# GND_SATION_PCB_1_02.net
KiCad netlist of a schematic drawn in EAGLE
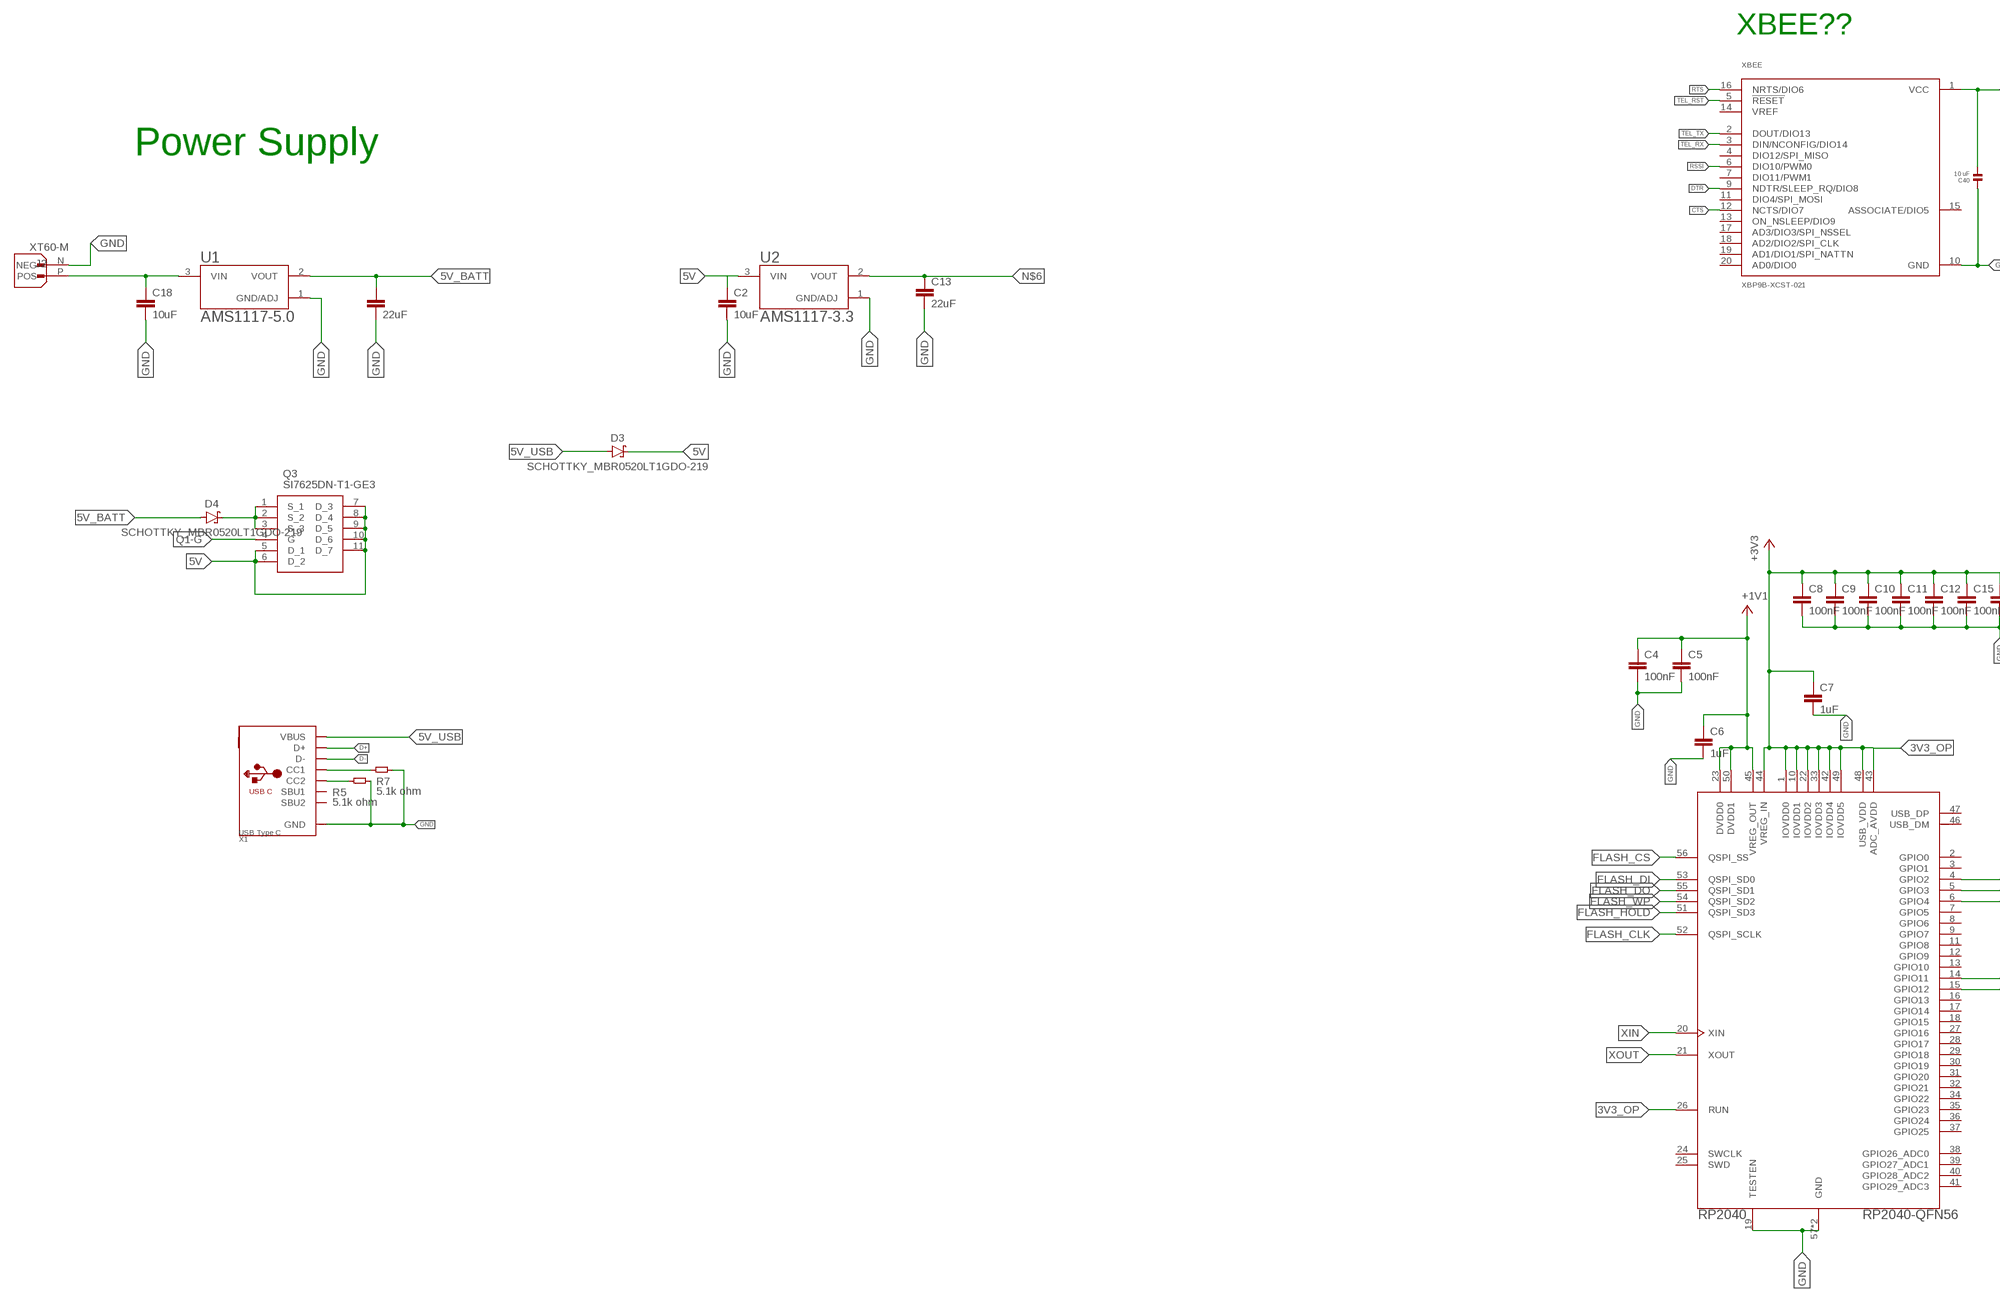
[diagram p0: schematic, sheet 1, part 1 of 2]
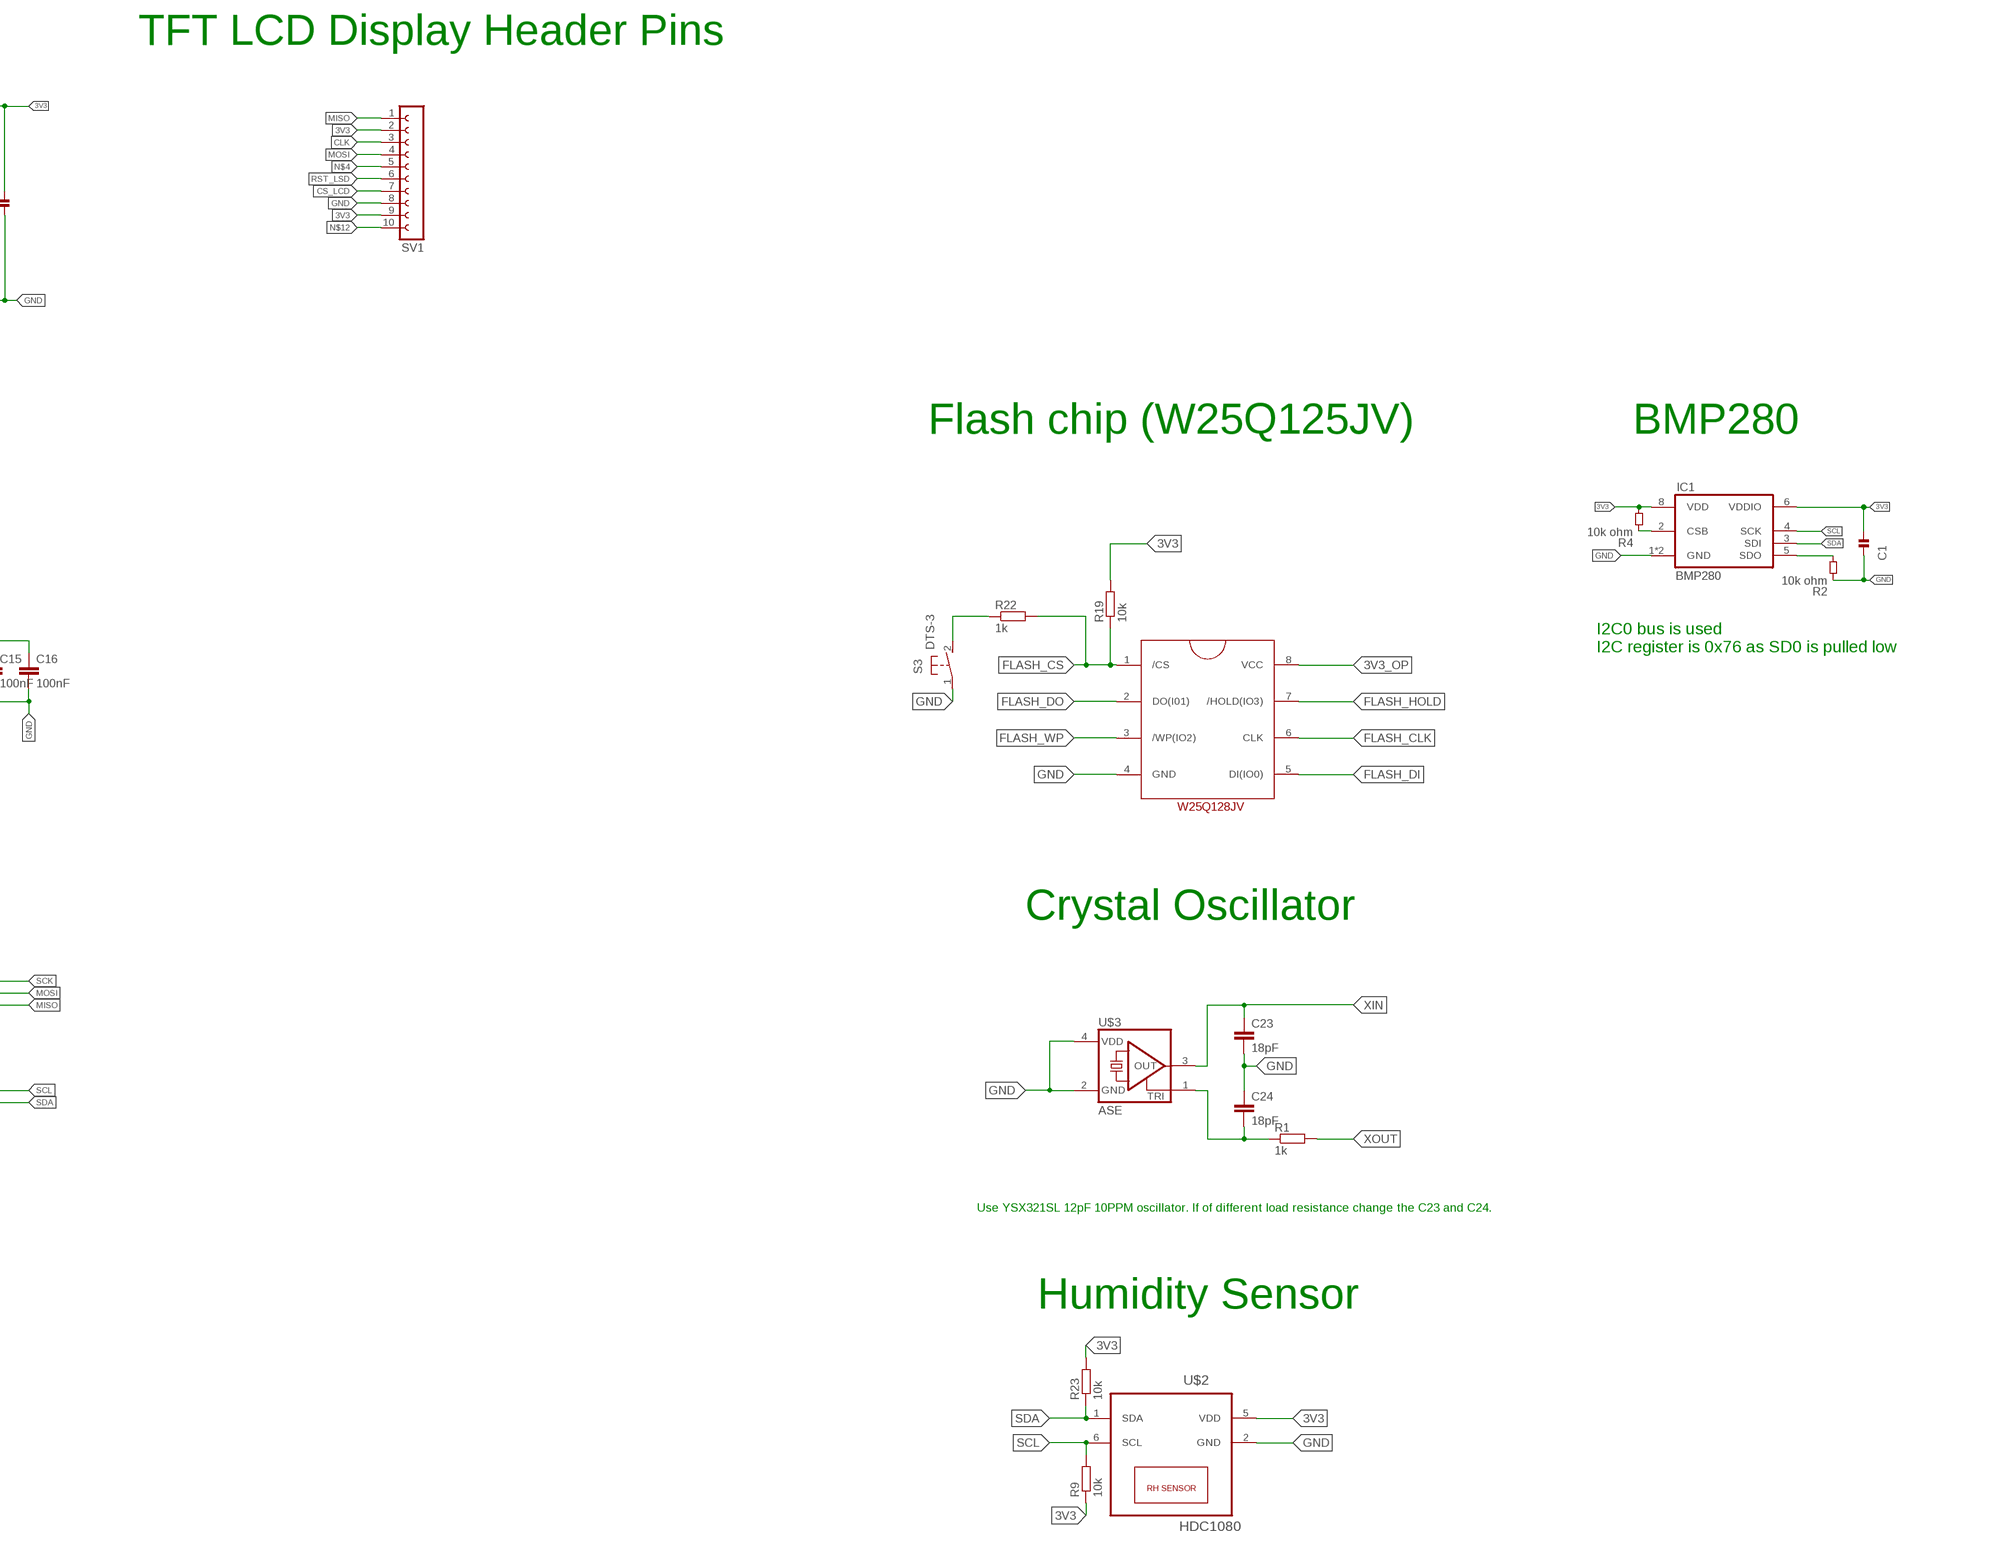
[diagram p1: schematic, sheet 1, part 2 of 2]

(export (version "E")
  (design (tool "Eeschema 10.0.6"))
  (components
    (comp (ref "C1")
      (value "10 uF")
      (footprint "eagle-import:0603")
      (libsource (lib "eagle-import") (part "CAPACITOR.0603"))
    )
    (comp (ref "C2")
      (value "10uF")
      (footprint "eagle-import:C0805")
      (libsource (lib "eagle-import") (part "C-EUC0805"))
    )
    (comp (ref "C3")
      (value "22uF")
      (footprint "eagle-import:C0805")
      (libsource (lib "eagle-import") (part "C-EUC0805"))
    )
    (comp (ref "C4")
      (value "100nF")
      (footprint "eagle-import:C0603")
      (libsource (lib "eagle-import") (part "C-EUC0603"))
    )
    (comp (ref "C5")
      (value "100nF")
      (footprint "eagle-import:C0603")
      (libsource (lib "eagle-import") (part "C-EUC0603"))
    )
    (comp (ref "C6")
      (value "1uF")
      (footprint "eagle-import:C0603")
      (libsource (lib "eagle-import") (part "C-EUC0603"))
    )
    (comp (ref "C7")
      (value "1uF")
      (footprint "eagle-import:C0603")
      (libsource (lib "eagle-import") (part "C-EUC0603"))
    )
    (comp (ref "C8")
      (value "100nF")
      (footprint "eagle-import:C0603")
      (libsource (lib "eagle-import") (part "C-EUC0603"))
    )
    (comp (ref "C9")
      (value "100nF")
      (footprint "eagle-import:C0603")
      (libsource (lib "eagle-import") (part "C-EUC0603"))
    )
    (comp (ref "C10")
      (value "100nF")
      (footprint "eagle-import:C0603")
      (libsource (lib "eagle-import") (part "C-EUC0603"))
    )
    (comp (ref "C11")
      (value "100nF")
      (footprint "eagle-import:C0603")
      (libsource (lib "eagle-import") (part "C-EUC0603"))
    )
    (comp (ref "C12")
      (value "100nF")
      (footprint "eagle-import:C0603")
      (libsource (lib "eagle-import") (part "C-EUC0603"))
    )
    (comp (ref "C13")
      (value "22uF")
      (footprint "eagle-import:C0805")
      (libsource (lib "eagle-import") (part "C-EUC0805"))
    )
    (comp (ref "C15")
      (value "100nF")
      (footprint "eagle-import:C0603")
      (libsource (lib "eagle-import") (part "C-EUC0603"))
    )
    (comp (ref "C16")
      (value "100nF")
      (footprint "eagle-import:C0603")
      (libsource (lib "eagle-import") (part "C-EUC0603"))
    )
    (comp (ref "C18")
      (value "10uF")
      (footprint "eagle-import:C0805")
      (libsource (lib "eagle-import") (part "C-EUC0805"))
    )
    (comp (ref "C23")
      (value "18pF")
      (footprint "eagle-import:C0805")
      (libsource (lib "eagle-import") (part "C-EUC0805"))
    )
    (comp (ref "C24")
      (value "18pF")
      (footprint "eagle-import:C0805")
      (libsource (lib "eagle-import") (part "C-EUC0805"))
    )
    (comp (ref "C40")
      (value "10 uF")
      (footprint "eagle-import:0603")
      (libsource (lib "eagle-import") (part "CAPACITOR.0603"))
    )
    (comp (ref "D3")
      (value "SCHOTTKY_MBR0520LT1GDO-219")
      (footprint "eagle-import:SODFL3718X115")
      (fields (field (name "MANUFACTURER") "onsemi") (field (name "MPN") "MBR0520LT1G"))
      (libsource (lib "eagle-import") (part "SCHOTTKY_DO-219MBR0520LT1G"))
    )
    (comp (ref "D4")
      (value "SCHOTTKY_MBR0520LT1GDO-219")
      (footprint "eagle-import:SODFL3718X115")
      (fields (field (name "MANUFACTURER") "onsemi") (field (name "MPN") "MBR0520LT1G"))
      (libsource (lib "eagle-import") (part "SCHOTTKY_DO-219MBR0520LT1G"))
    )
    (comp (ref "IC1")
      (value "BMP280")
      (footprint "eagle-import:BMP280")
      (libsource (lib "eagle-import") (part "BMP280"))
    )
    (comp (ref "J2")
      (value "XT60-M")
      (footprint "eagle-import:AMASS_XT60-M")
      (fields (field (name "MF") "AMASS"))
      (libsource (lib "eagle-import") (part "XT60-M"))
    )
    (comp (ref "Q3")
      (value "SI7625DN-T1-GE3")
      (footprint "eagle-import:SIS862DNT1GE3")
      (libsource (lib "eagle-import") (part "SI7625DN-T1-GE3"))
    )
    (comp (ref "R1")
      (value "1k")
      (footprint "eagle-import:R0805")
      (libsource (lib "eagle-import") (part "R-EU_R0805"))
    )
    (comp (ref "R2")
      (value "10k ohm")
      (footprint "eagle-import:0603")
      (libsource (lib "eagle-import") (part "RESISTOR.0603"))
    )
    (comp (ref "R4")
      (value "10k ohm")
      (footprint "eagle-import:0603")
      (libsource (lib "eagle-import") (part "RESISTOR.0603"))
    )
    (comp (ref "R5")
      (value "5.1k ohm")
      (footprint "eagle-import:0603")
      (libsource (lib "eagle-import") (part "RESISTOR.0603"))
    )
    (comp (ref "R7")
      (value "5.1k ohm")
      (footprint "eagle-import:0603")
      (libsource (lib "eagle-import") (part "RESISTOR.0603"))
    )
    (comp (ref "R9")
      (value "10k")
      (footprint "eagle-import:R0805")
      (libsource (lib "eagle-import") (part "R-EU_R0805"))
    )
    (comp (ref "R19")
      (value "10k")
      (footprint "eagle-import:R0805")
      (libsource (lib "eagle-import") (part "R-EU_R0805"))
    )
    (comp (ref "R22")
      (value "1k")
      (footprint "eagle-import:R0805")
      (libsource (lib "eagle-import") (part "R-EU_R0805"))
    )
    (comp (ref "R23")
      (value "10k")
      (footprint "eagle-import:R0805")
      (libsource (lib "eagle-import") (part "R-EU_R0805"))
    )
    (comp (ref "RP2040")
      (value "RP2040-QFN56")
      (footprint "eagle-import:RP2040-QFN-56")
      (libsource (lib "eagle-import") (part "RP2040-QFN56"))
    )
    (comp (ref "S3")
      (value "DTS-3")
      (footprint "eagle-import:DTS-3")
      (fields (field (name "MF") "APEM Inc."))
      (libsource (lib "eagle-import") (part "DTS-3"))
    )
    (comp (ref "SV1")
      (value "FE10-1")
      (footprint "eagle-import:FE10")
      (libsource (lib "eagle-import") (part "FE10-1"))
    )
    (comp (ref "U$2")
      (value "HDC1080")
      (footprint "eagle-import:TI-S-PWSON-N6")
      (libsource (lib "eagle-import") (part "HDC1080"))
    )
    (comp (ref "U$3")
      (value "ASE")
      (footprint "eagle-import:ASE")
      (libsource (lib "eagle-import") (part "ASE"))
    )
    (comp (ref "U1")
      (value "AMS1117-5.0")
      (footprint "eagle-import:SOT229P700X180-4N")
      (fields (field (name "MF") "Advanced Monolithic Systems"))
      (libsource (lib "eagle-import") (part "AMS1117-5.0"))
    )
    (comp (ref "U2")
      (value "AMS1117-3.3")
      (footprint "eagle-import:SOT229P700X180-4N")
      (fields (field (name "MF") "Advanced Monolithic Systems"))
      (libsource (lib "eagle-import") (part "AMS1117-3.3"))
    )
    (comp (ref "U4")
      (value "SOIC127P790X216-8NW25Q128JVJSQ")
      (footprint "eagle-import:SOIC127P790X216-8N")
      (libsource (lib "eagle-import") (part "SOIC127P790X216-8NW25Q128JVJSQ"))
    )
    (comp (ref "X1")
      (value "USB Type C")
      (footprint "eagle-import:USB_C_CUSB31-CFM2AX-01-X")
      (libsource (lib "eagle-import") (part "USB_C"))
    )
    (comp (ref "XBEE")
      (value "XBP9B-XCST-021")
      (footprint "eagle-import:DIP2200W51P200L3294H279Q20P")
      (fields (field (name "MF") "Digi International"))
      (libsource (lib "eagle-import") (part "XBP9B-XCST-021"))
    )
  )
  (nets
    (net (code "1") (name "+1V1") (class "Default")
      (node (ref "C4") (pin "1") (pinfunction "1_1") (pintype "passive"))
      (node (ref "C5") (pin "1") (pinfunction "1_1") (pintype "passive"))
      (node (ref "C6") (pin "1") (pinfunction "1_1") (pintype "passive"))
      (node (ref "RP2040") (pin "23") (pinfunction "DVDD0_23") (pintype "power_in"))
      (node (ref "RP2040") (pin "45") (pinfunction "VREG_OUT_45") (pintype "power_in"))
      (node (ref "RP2040") (pin "50") (pinfunction "DVDD1_50") (pintype "power_in"))
    )
    (net (code "2") (name "3V3") (class "Default")
      (node (ref "C1") (pin "2") (pinfunction "2_2") (pintype "bidirectional"))
      (node (ref "C40") (pin "2") (pinfunction "2_2") (pintype "bidirectional"))
      (node (ref "IC1") (pin "6") (pinfunction "VDDIO_6") (pintype "power_in"))
      (node (ref "IC1") (pin "8") (pinfunction "VDD_8") (pintype "power_in"))
      (node (ref "R19") (pin "2") (pinfunction "2_2") (pintype "passive"))
      (node (ref "R23") (pin "2") (pinfunction "2_2") (pintype "passive"))
      (node (ref "R4") (pin "2") (pinfunction "2_2") (pintype "bidirectional"))
      (node (ref "R9") (pin "1") (pinfunction "1_1") (pintype "passive"))
      (node (ref "SV1") (pin "2") (pinfunction "2_2") (pintype "passive"))
      (node (ref "SV1") (pin "9") (pinfunction "9_9") (pintype "passive"))
      (node (ref "U$2") (pin "5") (pinfunction "VDD_5") (pintype "output"))
      (node (ref "XBEE") (pin "1") (pinfunction "VCC_1") (pintype "power_in"))
    )
    (net (code "3") (name "3V3_OP") (class "Default")
      (node (ref "C10") (pin "1") (pinfunction "1_1") (pintype "passive"))
      (node (ref "C11") (pin "1") (pinfunction "1_1") (pintype "passive"))
      (node (ref "C12") (pin "1") (pinfunction "1_1") (pintype "passive"))
      (node (ref "C15") (pin "1") (pinfunction "1_1") (pintype "passive"))
      (node (ref "C16") (pin "1") (pinfunction "1_1") (pintype "passive"))
      (node (ref "C7") (pin "1") (pinfunction "1_1") (pintype "passive"))
      (node (ref "C8") (pin "1") (pinfunction "1_1") (pintype "passive"))
      (node (ref "C9") (pin "1") (pinfunction "1_1") (pintype "passive"))
      (node (ref "RP2040") (pin "1") (pinfunction "IOVDD0_1") (pintype "power_in"))
      (node (ref "RP2040") (pin "10") (pinfunction "IOVDD1_10") (pintype "power_in"))
      (node (ref "RP2040") (pin "22") (pinfunction "IOVDD2_22") (pintype "power_in"))
      (node (ref "RP2040") (pin "26") (pinfunction "RUN_26") (pintype "input"))
      (node (ref "RP2040") (pin "33") (pinfunction "IOVDD3_33") (pintype "power_in"))
      (node (ref "RP2040") (pin "42") (pinfunction "IOVDD4_42") (pintype "power_in"))
      (node (ref "RP2040") (pin "43") (pinfunction "ADC_AVDD_43") (pintype "power_in"))
      (node (ref "RP2040") (pin "44") (pinfunction "VREG_IN_44") (pintype "power_in"))
      (node (ref "RP2040") (pin "48") (pinfunction "USB_VDD_48") (pintype "power_in"))
      (node (ref "RP2040") (pin "49") (pinfunction "IOVDD5_49") (pintype "power_in"))
      (node (ref "U4") (pin "8") (pinfunction "VCC_8") (pintype "bidirectional"))
    )
    (net (code "4") (name "5V") (class "Default")
      (node (ref "D3") (pin "1") (pinfunction "C_1") (pintype "passive"))
      (node (ref "Q3") (pin "10") (pinfunction "D_6_10") (pintype "bidirectional"))
      (node (ref "Q3") (pin "11") (pinfunction "D_7_11") (pintype "bidirectional"))
      (node (ref "Q3") (pin "5") (pinfunction "D_1_5") (pintype "bidirectional"))
      (node (ref "Q3") (pin "6") (pinfunction "D_2_6") (pintype "bidirectional"))
      (node (ref "Q3") (pin "7") (pinfunction "D_3_7") (pintype "bidirectional"))
      (node (ref "Q3") (pin "8") (pinfunction "D_4_8") (pintype "bidirectional"))
      (node (ref "Q3") (pin "9") (pinfunction "D_5_9") (pintype "bidirectional"))
      (node (ref "U2") (pin "3") (pinfunction "VIN_3") (pintype "input"))
    )
    (net (code "5") (name "5V_BATT") (class "Default")
      (node (ref "C3") (pin "1") (pinfunction "1_1") (pintype "passive"))
      (node (ref "D4") (pin "1") (pinfunction "C_1") (pintype "passive"))
      (node (ref "Q3") (pin "1") (pinfunction "S_1_1") (pintype "bidirectional"))
      (node (ref "Q3") (pin "2") (pinfunction "S_2_2") (pintype "bidirectional"))
      (node (ref "Q3") (pin "3") (pinfunction "S_3_3") (pintype "bidirectional"))
      (node (ref "U1") (pin "2") (pinfunction "VOUT_2") (pintype "output"))
    )
    (net (code "6") (name "5V_USB") (class "Default")
      (node (ref "D3") (pin "2") (pinfunction "A_2") (pintype "passive"))
      (node (ref "X1") (pin "A4B9") (pinfunction "VBUS_A4B9") (pintype "power_in"))
      (node (ref "X1") (pin "B4A9") (pinfunction "VBUS_B4A9") (pintype "power_in"))
    )
    (net (code "7") (name "CLK") (class "Default")
      (node (ref "SV1") (pin "3") (pinfunction "3_3") (pintype "passive"))
    )
    (net (code "8") (name "CS_LCD") (class "Default")
      (node (ref "SV1") (pin "7") (pinfunction "7_7") (pintype "passive"))
    )
    (net (code "9") (name "CTS") (class "Default")
      (node (ref "XBEE") (pin "12") (pinfunction "NCTS/DIO7_12") (pintype "bidirectional"))
    )
    (net (code "10") (name "D+") (class "Default")
      (node (ref "X1") (pin "A6") (pinfunction "D+_A6") (pintype "bidirectional"))
      (node (ref "X1") (pin "B6") (pinfunction "D+_B6") (pintype "bidirectional"))
    )
    (net (code "11") (name "D-") (class "Default")
      (node (ref "X1") (pin "A7") (pinfunction "D-_A7") (pintype "bidirectional"))
      (node (ref "X1") (pin "B7") (pinfunction "D-_B7") (pintype "bidirectional"))
    )
    (net (code "12") (name "DTR") (class "Default")
      (node (ref "XBEE") (pin "9") (pinfunction "NDTR/SLEEP_RQ/DIO8_9") (pintype "bidirectional"))
    )
    (net (code "13") (name "FLASH_CLK") (class "Default")
      (node (ref "RP2040") (pin "52") (pinfunction "QSPI_SCLK_52") (pintype "output"))
      (node (ref "U4") (pin "6") (pinfunction "CLK_6") (pintype "bidirectional"))
    )
    (net (code "14") (name "FLASH_CS") (class "Default")
      (node (ref "R19") (pin "1") (pinfunction "1_1") (pintype "passive"))
      (node (ref "R22") (pin "2") (pinfunction "2_2") (pintype "passive"))
      (node (ref "RP2040") (pin "56") (pinfunction "QSPI_SS_56") (pintype "bidirectional"))
      (node (ref "U4") (pin "1") (pinfunction "/CS_1") (pintype "bidirectional"))
    )
    (net (code "15") (name "FLASH_DI") (class "Default")
      (node (ref "RP2040") (pin "53") (pinfunction "QSPI_SD0_53") (pintype "bidirectional"))
      (node (ref "U4") (pin "5") (pinfunction "DI(IO0)_5") (pintype "bidirectional"))
    )
    (net (code "16") (name "FLASH_DO") (class "Default")
      (node (ref "RP2040") (pin "55") (pinfunction "QSPI_SD1_55") (pintype "bidirectional"))
      (node (ref "U4") (pin "2") (pinfunction "DO(I01)_2") (pintype "bidirectional"))
    )
    (net (code "17") (name "FLASH_HOLD") (class "Default")
      (node (ref "RP2040") (pin "51") (pinfunction "QSPI_SD3_51") (pintype "bidirectional"))
      (node (ref "U4") (pin "7") (pinfunction "/HOLD(IO3)_7") (pintype "bidirectional"))
    )
    (net (code "18") (name "FLASH_WP") (class "Default")
      (node (ref "RP2040") (pin "54") (pinfunction "QSPI_SD2_54") (pintype "bidirectional"))
      (node (ref "U4") (pin "3") (pinfunction "/WP(IO2)_3") (pintype "bidirectional"))
    )
    (net (code "19") (name "GND") (class "Default")
      (node (ref "C1") (pin "1") (pinfunction "1_1") (pintype "bidirectional"))
      (node (ref "C10") (pin "2") (pinfunction "2_2") (pintype "passive"))
      (node (ref "C11") (pin "2") (pinfunction "2_2") (pintype "passive"))
      (node (ref "C12") (pin "2") (pinfunction "2_2") (pintype "passive"))
      (node (ref "C13") (pin "2") (pinfunction "2_2") (pintype "passive"))
      (node (ref "C15") (pin "2") (pinfunction "2_2") (pintype "passive"))
      (node (ref "C16") (pin "2") (pinfunction "2_2") (pintype "passive"))
      (node (ref "C18") (pin "2") (pinfunction "2_2") (pintype "passive"))
      (node (ref "C2") (pin "2") (pinfunction "2_2") (pintype "passive"))
      (node (ref "C23") (pin "2") (pinfunction "2_2") (pintype "passive"))
      (node (ref "C24") (pin "1") (pinfunction "1_1") (pintype "passive"))
      (node (ref "C3") (pin "2") (pinfunction "2_2") (pintype "passive"))
      (node (ref "C4") (pin "2") (pinfunction "2_2") (pintype "passive"))
      (node (ref "C40") (pin "1") (pinfunction "1_1") (pintype "bidirectional"))
      (node (ref "C5") (pin "2") (pinfunction "2_2") (pintype "passive"))
      (node (ref "C6") (pin "2") (pinfunction "2_2") (pintype "passive"))
      (node (ref "C7") (pin "2") (pinfunction "2_2") (pintype "passive"))
      (node (ref "C8") (pin "2") (pinfunction "2_2") (pintype "passive"))
      (node (ref "C9") (pin "2") (pinfunction "2_2") (pintype "passive"))
      (node (ref "IC1") (pin "1") (pinfunction "GND_1") (pintype "power_in"))
      (node (ref "IC1") (pin "7") (pinfunction "GND_7") (pintype "power_in"))
      (node (ref "J2") (pin "N") (pinfunction "NEG_N") (pintype "passive"))
      (node (ref "R2") (pin "1") (pinfunction "1_1") (pintype "bidirectional"))
      (node (ref "R5") (pin "2") (pinfunction "2_2") (pintype "bidirectional"))
      (node (ref "R7") (pin "2") (pinfunction "2_2") (pintype "bidirectional"))
      (node (ref "RP2040") (pin "19") (pinfunction "TESTEN_19") (pintype "passive"))
      (node (ref "RP2040") (pin "57") (pinfunction "GND_57") (pintype "power_in"))
      (node (ref "RP2040") (pin "62") (pinfunction "GND_62") (pintype "power_in"))
      (node (ref "S3") (pin "1") (pinfunction "1_1") (pintype "passive"))
      (node (ref "SV1") (pin "8") (pinfunction "8_8") (pintype "passive"))
      (node (ref "U$2") (pin "2") (pinfunction "GND_2") (pintype "passive"))
      (node (ref "U$3") (pin "2") (pinfunction "GND_2") (pintype "power_in"))
      (node (ref "U$3") (pin "4") (pinfunction "VDD_4") (pintype "power_in"))
      (node (ref "U1") (pin "1") (pinfunction "GND/ADJ_1") (pintype "power_in"))
      (node (ref "U2") (pin "1") (pinfunction "GND/ADJ_1") (pintype "power_in"))
      (node (ref "U4") (pin "4") (pinfunction "GND_4") (pintype "bidirectional"))
      (node (ref "X1") (pin "A1B12") (pinfunction "GND_A1B12") (pintype "power_in"))
      (node (ref "X1") (pin "B1A12") (pinfunction "GND_B1A12") (pintype "power_in"))
      (node (ref "XBEE") (pin "10") (pinfunction "GND_10") (pintype "power_in"))
    )
    (net (code "20") (name "MISO") (class "Default")
      (node (ref "RP2040") (pin "6") (pinfunction "GPIO4_6") (pintype "bidirectional"))
      (node (ref "SV1") (pin "1") (pinfunction "1_1") (pintype "passive"))
    )
    (net (code "21") (name "MOSI") (class "Default")
      (node (ref "RP2040") (pin "5") (pinfunction "GPIO3_5") (pintype "bidirectional"))
      (node (ref "SV1") (pin "4") (pinfunction "4_4") (pintype "passive"))
    )
    (net (code "22") (name "N$4") (class "Default")
      (node (ref "SV1") (pin "5") (pinfunction "5_5") (pintype "passive"))
    )
    (net (code "23") (name "N$6") (class "Default")
      (node (ref "C13") (pin "1") (pinfunction "1_1") (pintype "passive"))
      (node (ref "U2") (pin "2") (pinfunction "VOUT_2") (pintype "output"))
    )
    (net (code "24") (name "N$12") (class "Default")
      (node (ref "SV1") (pin "10") (pinfunction "10_10") (pintype "passive"))
    )
    (net (code "25") (name "Net-(IC1-CSB)") (class "Default")
      (node (ref "IC1") (pin "2") (pinfunction "CSB_2") (pintype "input"))
      (node (ref "R4") (pin "1") (pinfunction "1_1") (pintype "bidirectional"))
    )
    (net (code "26") (name "Net-(IC1-SDO)") (class "Default")
      (node (ref "IC1") (pin "5") (pinfunction "SDO_5") (pintype "input"))
      (node (ref "R2") (pin "2") (pinfunction "2_2") (pintype "bidirectional"))
    )
    (net (code "27") (name "Net-(J2-POS)") (class "Default")
      (node (ref "C18") (pin "1") (pinfunction "1_1") (pintype "passive"))
      (node (ref "J2") (pin "P") (pinfunction "POS_P") (pintype "passive"))
      (node (ref "U1") (pin "3") (pinfunction "VIN_3") (pintype "input"))
    )
    (net (code "28") (name "Net-(R22-Pad1)") (class "Default")
      (node (ref "R22") (pin "1") (pinfunction "1_1") (pintype "passive"))
      (node (ref "S3") (pin "2") (pinfunction "2_2") (pintype "passive"))
    )
    (net (code "29") (name "Net-(X1-CC1)") (class "Default")
      (node (ref "R7") (pin "1") (pinfunction "1_1") (pintype "bidirectional"))
      (node (ref "X1") (pin "A5") (pinfunction "CC1_A5") (pintype "bidirectional"))
    )
    (net (code "30") (name "Net-(X1-CC2)") (class "Default")
      (node (ref "R5") (pin "1") (pinfunction "1_1") (pintype "bidirectional"))
      (node (ref "X1") (pin "B5") (pinfunction "CC2_B5") (pintype "bidirectional"))
    )
    (net (code "31") (name "Q1-G") (class "Default")
      (node (ref "Q3") (pin "4") (pinfunction "G_4") (pintype "bidirectional"))
    )
    (net (code "32") (name "RSSI") (class "Default")
      (node (ref "XBEE") (pin "6") (pinfunction "DIO10/PWM0_6") (pintype "bidirectional"))
    )
    (net (code "33") (name "RST_LSD") (class "Default")
      (node (ref "SV1") (pin "6") (pinfunction "6_6") (pintype "passive"))
    )
    (net (code "34") (name "RTS") (class "Default")
      (node (ref "XBEE") (pin "16") (pinfunction "NRTS/DIO6_16") (pintype "input"))
    )
    (net (code "35") (name "SCK") (class "Default")
      (node (ref "RP2040") (pin "4") (pinfunction "GPIO2_4") (pintype "bidirectional"))
    )
    (net (code "36") (name "SCL") (class "Default")
      (node (ref "IC1") (pin "4") (pinfunction "SCK_4") (pintype "bidirectional"))
      (node (ref "R9") (pin "2") (pinfunction "2_2") (pintype "passive"))
      (node (ref "RP2040") (pin "14") (pinfunction "GPIO11_14") (pintype "bidirectional"))
      (node (ref "U$2") (pin "6") (pinfunction "SCL_6") (pintype "passive"))
    )
    (net (code "37") (name "SDA") (class "Default")
      (node (ref "IC1") (pin "3") (pinfunction "SDI_3") (pintype "bidirectional"))
      (node (ref "R23") (pin "1") (pinfunction "1_1") (pintype "passive"))
      (node (ref "RP2040") (pin "15") (pinfunction "GPIO12_15") (pintype "bidirectional"))
      (node (ref "U$2") (pin "1") (pinfunction "SDA_1") (pintype "power_in"))
    )
    (net (code "38") (name "TEL_RST") (class "Default")
      (node (ref "XBEE") (pin "5") (pinfunction "~{RESET}_5") (pintype "input"))
    )
    (net (code "39") (name "TEL_RX") (class "Default")
      (node (ref "XBEE") (pin "3") (pinfunction "DIN/NCONFIG/DIO14_3") (pintype "bidirectional"))
    )
    (net (code "40") (name "TEL_TX") (class "Default")
      (node (ref "XBEE") (pin "2") (pinfunction "DOUT/DIO13_2") (pintype "bidirectional"))
    )
    (net (code "41") (name "XIN") (class "Default")
      (node (ref "C23") (pin "1") (pinfunction "1_1") (pintype "passive"))
      (node (ref "RP2040") (pin "20") (pinfunction "XIN_20") (pintype "input"))
      (node (ref "U$3") (pin "3") (pinfunction "OUT_3") (pintype "output"))
    )
    (net (code "42") (name "XOUT") (class "Default")
      (node (ref "C24") (pin "2") (pinfunction "2_2") (pintype "passive"))
      (node (ref "R1") (pin "1") (pinfunction "1_1") (pintype "passive"))
      (node (ref "R1") (pin "2") (pinfunction "2_2") (pintype "passive"))
      (node (ref "RP2040") (pin "21") (pinfunction "XOUT_21") (pintype "passive"))
      (node (ref "U$3") (pin "1") (pinfunction "TRI_1") (pintype "input"))
    )
    (net (code "43") (name "unconnected-(C2-Pad1)") (class "Default")
      (node (ref "C2") (pin "1") (pinfunction "1_1") (pintype "passive"))
    )
    (net (code "44") (name "unconnected-(D4-A-Pad2)") (class "Default")
      (node (ref "D4") (pin "2") (pinfunction "A_2") (pintype "passive"))
    )
    (net (code "45") (name "unconnected-(RP2040-GPIO0-Pad2)") (class "Default")
      (node (ref "RP2040") (pin "2") (pinfunction "GPIO0_2") (pintype "bidirectional"))
    )
    (net (code "46") (name "unconnected-(RP2040-GPIO1-Pad3)") (class "Default")
      (node (ref "RP2040") (pin "3") (pinfunction "GPIO1_3") (pintype "bidirectional"))
    )
    (net (code "47") (name "unconnected-(RP2040-GPIO5-Pad7)") (class "Default")
      (node (ref "RP2040") (pin "7") (pinfunction "GPIO5_7") (pintype "bidirectional"))
    )
    (net (code "48") (name "unconnected-(RP2040-GPIO6-Pad8)") (class "Default")
      (node (ref "RP2040") (pin "8") (pinfunction "GPIO6_8") (pintype "bidirectional"))
    )
    (net (code "49") (name "unconnected-(RP2040-GPIO7-Pad9)") (class "Default")
      (node (ref "RP2040") (pin "9") (pinfunction "GPIO7_9") (pintype "bidirectional"))
    )
    (net (code "50") (name "unconnected-(RP2040-GPIO8-Pad11)") (class "Default")
      (node (ref "RP2040") (pin "11") (pinfunction "GPIO8_11") (pintype "bidirectional"))
    )
    (net (code "51") (name "unconnected-(RP2040-GPIO9-Pad12)") (class "Default")
      (node (ref "RP2040") (pin "12") (pinfunction "GPIO9_12") (pintype "bidirectional"))
    )
    (net (code "52") (name "unconnected-(RP2040-GPIO10-Pad13)") (class "Default")
      (node (ref "RP2040") (pin "13") (pinfunction "GPIO10_13") (pintype "bidirectional"))
    )
    (net (code "53") (name "unconnected-(RP2040-GPIO13-Pad16)") (class "Default")
      (node (ref "RP2040") (pin "16") (pinfunction "GPIO13_16") (pintype "bidirectional"))
    )
    (net (code "54") (name "unconnected-(RP2040-GPIO14-Pad17)") (class "Default")
      (node (ref "RP2040") (pin "17") (pinfunction "GPIO14_17") (pintype "bidirectional"))
    )
    (net (code "55") (name "unconnected-(RP2040-GPIO15-Pad18)") (class "Default")
      (node (ref "RP2040") (pin "18") (pinfunction "GPIO15_18") (pintype "bidirectional"))
    )
    (net (code "56") (name "unconnected-(RP2040-GPIO16-Pad27)") (class "Default")
      (node (ref "RP2040") (pin "27") (pinfunction "GPIO16_27") (pintype "bidirectional"))
    )
    (net (code "57") (name "unconnected-(RP2040-GPIO17-Pad28)") (class "Default")
      (node (ref "RP2040") (pin "28") (pinfunction "GPIO17_28") (pintype "bidirectional"))
    )
    (net (code "58") (name "unconnected-(RP2040-GPIO18-Pad29)") (class "Default")
      (node (ref "RP2040") (pin "29") (pinfunction "GPIO18_29") (pintype "bidirectional"))
    )
    (net (code "59") (name "unconnected-(RP2040-GPIO19-Pad30)") (class "Default")
      (node (ref "RP2040") (pin "30") (pinfunction "GPIO19_30") (pintype "bidirectional"))
    )
    (net (code "60") (name "unconnected-(RP2040-GPIO20-Pad31)") (class "Default")
      (node (ref "RP2040") (pin "31") (pinfunction "GPIO20_31") (pintype "bidirectional"))
    )
    (net (code "61") (name "unconnected-(RP2040-GPIO21-Pad32)") (class "Default")
      (node (ref "RP2040") (pin "32") (pinfunction "GPIO21_32") (pintype "bidirectional"))
    )
    (net (code "62") (name "unconnected-(RP2040-GPIO22-Pad34)") (class "Default")
      (node (ref "RP2040") (pin "34") (pinfunction "GPIO22_34") (pintype "bidirectional"))
    )
    (net (code "63") (name "unconnected-(RP2040-GPIO23-Pad35)") (class "Default")
      (node (ref "RP2040") (pin "35") (pinfunction "GPIO23_35") (pintype "bidirectional"))
    )
    (net (code "64") (name "unconnected-(RP2040-GPIO24-Pad36)") (class "Default")
      (node (ref "RP2040") (pin "36") (pinfunction "GPIO24_36") (pintype "bidirectional"))
    )
    (net (code "65") (name "unconnected-(RP2040-GPIO25-Pad37)") (class "Default")
      (node (ref "RP2040") (pin "37") (pinfunction "GPIO25_37") (pintype "bidirectional"))
    )
    (net (code "66") (name "unconnected-(RP2040-GPIO26_ADC0-Pad38)") (class "Default")
      (node (ref "RP2040") (pin "38") (pinfunction "GPIO26_ADC0_38") (pintype "bidirectional"))
    )
    (net (code "67") (name "unconnected-(RP2040-GPIO27_ADC1-Pad39)") (class "Default")
      (node (ref "RP2040") (pin "39") (pinfunction "GPIO27_ADC1_39") (pintype "bidirectional"))
    )
    (net (code "68") (name "unconnected-(RP2040-GPIO28_ADC2-Pad40)") (class "Default")
      (node (ref "RP2040") (pin "40") (pinfunction "GPIO28_ADC2_40") (pintype "bidirectional"))
    )
    (net (code "69") (name "unconnected-(RP2040-GPIO29_ADC3-Pad41)") (class "Default")
      (node (ref "RP2040") (pin "41") (pinfunction "GPIO29_ADC3_41") (pintype "bidirectional"))
    )
    (net (code "70") (name "unconnected-(RP2040-SWCLK-Pad24)") (class "Default")
      (node (ref "RP2040") (pin "24") (pinfunction "SWCLK_24") (pintype "output"))
    )
    (net (code "71") (name "unconnected-(RP2040-SWD-Pad25)") (class "Default")
      (node (ref "RP2040") (pin "25") (pinfunction "SWD_25") (pintype "bidirectional"))
    )
    (net (code "72") (name "unconnected-(RP2040-USB_DM-Pad46)") (class "Default")
      (node (ref "RP2040") (pin "46") (pinfunction "USB_DM_46") (pintype "bidirectional"))
    )
    (net (code "73") (name "unconnected-(RP2040-USB_DP-Pad47)") (class "Default")
      (node (ref "RP2040") (pin "47") (pinfunction "USB_DP_47") (pintype "bidirectional"))
    )
    (net (code "74") (name "unconnected-(X1-SBU1-PadA8)") (class "Default")
      (node (ref "X1") (pin "A8") (pinfunction "SBU1_A8") (pintype "bidirectional"))
    )
    (net (code "75") (name "unconnected-(X1-SBU2-PadB8)") (class "Default")
      (node (ref "X1") (pin "B8") (pinfunction "SBU2_B8") (pintype "bidirectional"))
    )
    (net (code "76") (name "unconnected-(XBEE-AD0{slash}DIO0-Pad20)") (class "Default")
      (node (ref "XBEE") (pin "20") (pinfunction "AD0/DIO0_20") (pintype "bidirectional"))
    )
    (net (code "77") (name "unconnected-(XBEE-AD1{slash}DIO1{slash}SPI_NATTN-Pad19)") (class "Default")
      (node (ref "XBEE") (pin "19") (pinfunction "AD1/DIO1/SPI_NATTN_19") (pintype "bidirectional"))
    )
    (net (code "78") (name "unconnected-(XBEE-AD2{slash}DIO2{slash}SPI_CLK-Pad18)") (class "Default")
      (node (ref "XBEE") (pin "18") (pinfunction "AD2/DIO2/SPI_CLK_18") (pintype "bidirectional"))
    )
    (net (code "79") (name "unconnected-(XBEE-AD3{slash}DIO3{slash}SPI_NSSEL-Pad17)") (class "Default")
      (node (ref "XBEE") (pin "17") (pinfunction "AD3/DIO3/SPI_NSSEL_17") (pintype "bidirectional"))
    )
    (net (code "80") (name "unconnected-(XBEE-ASSOCIATE{slash}DIO5-Pad15)") (class "Default")
      (node (ref "XBEE") (pin "15") (pinfunction "ASSOCIATE/DIO5_15") (pintype "output"))
    )
    (net (code "81") (name "unconnected-(XBEE-DIO4{slash}SPI_MOSI-Pad11)") (class "Default")
      (node (ref "XBEE") (pin "11") (pinfunction "DIO4/SPI_MOSI_11") (pintype "bidirectional"))
    )
    (net (code "82") (name "unconnected-(XBEE-DIO11{slash}PWM1-Pad7)") (class "Default")
      (node (ref "XBEE") (pin "7") (pinfunction "DIO11/PWM1_7") (pintype "bidirectional"))
    )
    (net (code "83") (name "unconnected-(XBEE-DIO12{slash}SPI_MISO-Pad4)") (class "Default")
      (node (ref "XBEE") (pin "4") (pinfunction "DIO12/SPI_MISO_4") (pintype "bidirectional"))
    )
    (net (code "84") (name "unconnected-(XBEE-ON_NSLEEP{slash}DIO9-Pad13)") (class "Default")
      (node (ref "XBEE") (pin "13") (pinfunction "ON_NSLEEP/DIO9_13") (pintype "bidirectional"))
    )
    (net (code "85") (name "unconnected-(XBEE-VREF-Pad14)") (class "Default")
      (node (ref "XBEE") (pin "14") (pinfunction "VREF_14") (pintype "input"))
    )
  )
)
